# omnibothub-debug.net
KiCad netlist of a schematic drawn in Altium Designer
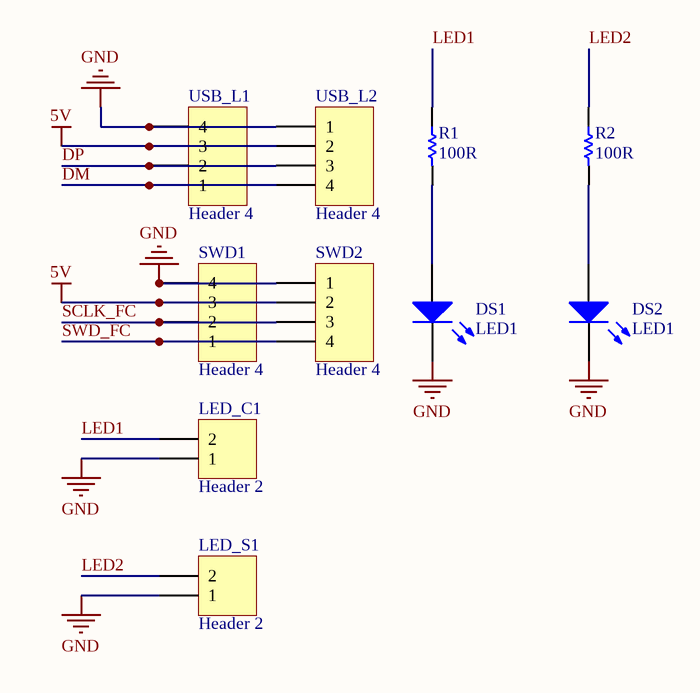
[diagram p0: omnibothub-debug.SchDoc]

(export (version "E")
  (design (tool "Eeschema 10.0.6"))
  (components
    (comp (ref "DS1")
      (value "LED1")
      (footprint "SMDLED")
      (description "Typical RED, GREEN, YELLOW, AMBER GaAs LED")
      (fields (field (name "PUBLISHER") "Altium Limited"))
      (libsource (lib "EXPLORER") (part "LED2"))
    )
    (comp (ref "DS2")
      (value "LED1")
      (footprint "SMDLED")
      (description "Typical RED, GREEN, YELLOW, AMBER GaAs LED")
      (fields (field (name "PUBLISHER") "Altium Limited"))
      (libsource (lib "EXPLORER") (part "LED2"))
    )
    (comp (ref "LED_C1")
      (value "Header 2")
      (footprint "GH1.25-2P")
      (description "Header, 2-Pin")
      (fields (field (name "PUBLISHER") "Altium Limited"))
      (libsource (lib "Miscellaneous Connectors") (part "Header 2"))
    )
    (comp (ref "LED_S1")
      (value "Header 2")
      (footprint "GH1.25-2P")
      (description "Header, 2-Pin")
      (fields (field (name "PUBLISHER") "Altium Limited"))
      (libsource (lib "Miscellaneous Connectors") (part "Header 2"))
    )
    (comp (ref "R1")
      (value "100R")
      (footprint "R 0402")
      (description "0603")
      (libsource (lib "stm32f429i") (part "Res2"))
    )
    (comp (ref "R2")
      (value "100R")
      (footprint "R 0402")
      (description "0603")
      (libsource (lib "stm32f429i") (part "Res2"))
    )
    (comp (ref "SWD1")
      (value "Header 4")
      (footprint "SH1.0-4P - up")
      (description "Header, 4-Pin")
      (fields (field (name "PUBLISHER") "Altium Limited"))
      (libsource (lib "Explorer STM32F407封装库") (part "Header 4"))
    )
    (comp (ref "SWD2")
      (value "Header 4")
      (footprint "SH1.0-4P - up")
      (description "Header, 4-Pin")
      (fields (field (name "PUBLISHER") "Altium Limited"))
      (libsource (lib "") (part "Header 4_1"))
    )
    (comp (ref "USB_L1")
      (value "Header 4")
      (footprint "SH1.0-4P - up")
      (description "Header, 4-Pin")
      (fields (field (name "PUBLISHER") "Altium Limited"))
      (libsource (lib "Explorer STM32F407封装库") (part "Header 4"))
    )
    (comp (ref "USB_L2")
      (value "Header 4")
      (footprint "SH1.0-4P - up")
      (description "Header, 4-Pin")
      (fields (field (name "PUBLISHER") "Altium Limited"))
      (libsource (lib "") (part "Header 4_1"))
    )
  )
  (nets
    (net (code "1") (name "/DM") (class "Default")
      (node (ref "USB_L1") (pin "1") (pinfunction "1_1") (pintype "passive"))
      (node (ref "USB_L2") (pin "4") (pinfunction "4_4") (pintype "passive"))
    )
    (net (code "2") (name "/DP") (class "Default")
      (node (ref "USB_L1") (pin "2") (pinfunction "2_2") (pintype "passive"))
      (node (ref "USB_L2") (pin "3") (pinfunction "3_3") (pintype "passive"))
    )
    (net (code "3") (name "/LED1") (class "Default")
      (node (ref "LED_C1") (pin "2") (pinfunction "2_2") (pintype "passive"))
      (node (ref "R1") (pin "1") (pinfunction "1_1") (pintype "passive"))
    )
    (net (code "4") (name "/LED2") (class "Default")
      (node (ref "LED_S1") (pin "2") (pinfunction "2_2") (pintype "passive"))
      (node (ref "R2") (pin "1") (pinfunction "1_1") (pintype "passive"))
    )
    (net (code "5") (name "/SCLK_FC") (class "Default")
      (node (ref "SWD1") (pin "2") (pinfunction "2_2") (pintype "passive"))
      (node (ref "SWD2") (pin "3") (pinfunction "3_3") (pintype "passive"))
    )
    (net (code "6") (name "/SWD_FC") (class "Default")
      (node (ref "SWD1") (pin "1") (pinfunction "1_1") (pintype "passive"))
      (node (ref "SWD2") (pin "4") (pinfunction "4_4") (pintype "passive"))
    )
    (net (code "7") (name "5V") (class "Default")
      (node (ref "SWD1") (pin "3") (pinfunction "3_3") (pintype "passive"))
      (node (ref "SWD2") (pin "2") (pinfunction "2_2") (pintype "passive"))
      (node (ref "USB_L1") (pin "3") (pinfunction "3_3") (pintype "passive"))
      (node (ref "USB_L2") (pin "2") (pinfunction "2_2") (pintype "passive"))
    )
    (net (code "8") (name "GND") (class "Default")
      (node (ref "DS1") (pin "2") (pinfunction "K_2") (pintype "passive"))
      (node (ref "DS2") (pin "2") (pinfunction "K_2") (pintype "passive"))
      (node (ref "LED_C1") (pin "1") (pinfunction "1_1") (pintype "passive"))
      (node (ref "LED_S1") (pin "1") (pinfunction "1_1") (pintype "passive"))
      (node (ref "SWD1") (pin "4") (pinfunction "4_4") (pintype "passive"))
      (node (ref "SWD2") (pin "1") (pinfunction "1_1") (pintype "passive"))
      (node (ref "USB_L1") (pin "4") (pinfunction "4_4") (pintype "passive"))
      (node (ref "USB_L2") (pin "1") (pinfunction "1_1") (pintype "passive"))
    )
    (net (code "9") (name "Net-(DS1-A)") (class "Default")
      (node (ref "DS1") (pin "1") (pinfunction "A_1") (pintype "passive"))
      (node (ref "R1") (pin "2") (pinfunction "2_2") (pintype "passive"))
    )
    (net (code "10") (name "Net-(DS2-A)") (class "Default")
      (node (ref "DS2") (pin "1") (pinfunction "A_1") (pintype "passive"))
      (node (ref "R2") (pin "2") (pinfunction "2_2") (pintype "passive"))
    )
  )
)
